# LED_DRIVE.net
KiCad netlist of a schematic drawn in Altium Designer
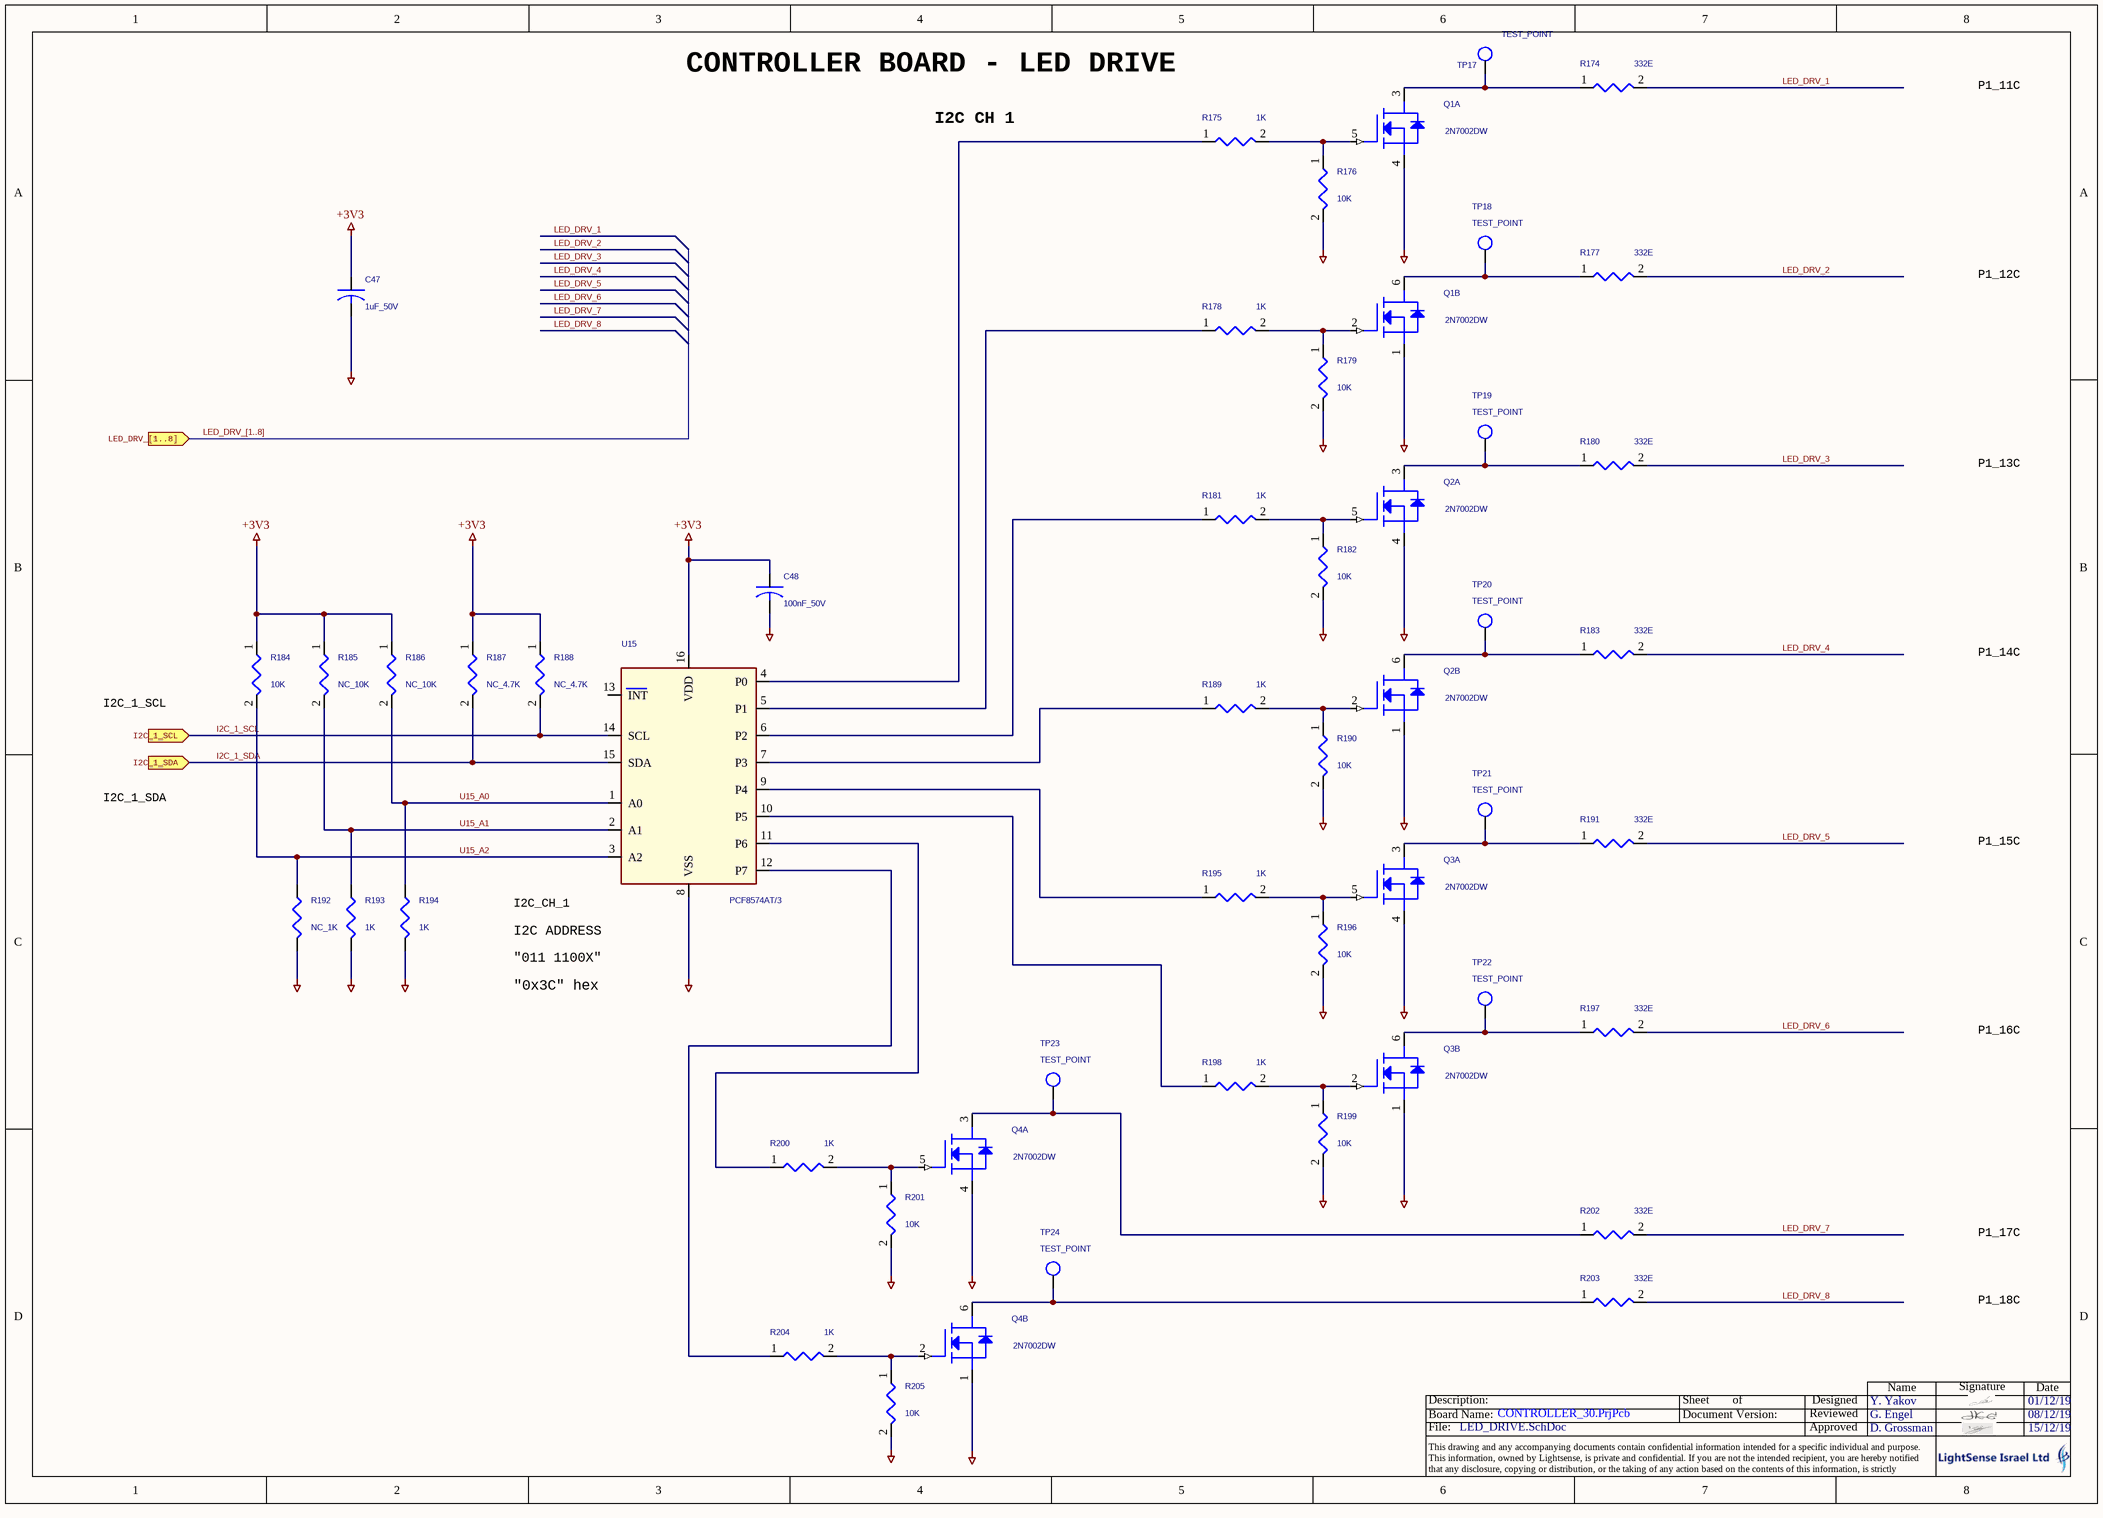
[diagram p0: LED_DRIVE.SchDoc]

(export (version "E")
  (design (tool "Eeschema 10.0.6"))
  (components
    (comp (ref "C47")
      (value "1uF_50V")
      (footprint "0805")
      (description "a")
      (fields (field (name "MFG") "Murata") (field (name "MNFCTR_PART_NUMBER") "TCJT106M016R0150"))
      (libsource (lib "*") (part "CAP"))
    )
    (comp (ref "C48")
      (value "100nF_50V")
      (footprint "0603")
      (description "CAP_SMT_0603_50V_X7R_10%")
      (fields (field (name "MFG") "KEMET"))
      (libsource (lib "*") (part "C"))
    )
    (comp (ref "Q1")
      (value "2N7002DW")
      (footprint "SOT_363")
      (fields (field (name "MFG") "DIODES"))
      (libsource (lib "*") (part "2N7002DW"))
    )
    (comp (ref "Q2")
      (value "2N7002DW")
      (footprint "SOT_363")
      (fields (field (name "MFG") "DIODES"))
      (libsource (lib "*") (part "2N7002DW"))
    )
    (comp (ref "Q3")
      (value "2N7002DW")
      (footprint "SOT_363")
      (fields (field (name "MFG") "DIODES"))
      (libsource (lib "*") (part "2N7002DW"))
    )
    (comp (ref "Q4")
      (value "2N7002DW")
      (footprint "SOT_363")
      (fields (field (name "MFG") "DIODES"))
      (libsource (lib "*") (part "2N7002DW"))
    )
    (comp (ref "R174")
      (value "332E")
      (footprint "R0603")
      (fields (field (name "MFG") "YAGEO"))
      (libsource (lib "*") (part "R"))
    )
    (comp (ref "R175")
      (value "1K")
      (footprint "R0603")
      (fields (field (name "MFG") "YAGEO"))
      (libsource (lib "*") (part "R"))
    )
    (comp (ref "R176")
      (value "10K")
      (footprint "R0603")
      (fields (field (name "MFG") "YAGEO"))
      (libsource (lib "*") (part "R"))
    )
    (comp (ref "R177")
      (value "332E")
      (footprint "R0603")
      (fields (field (name "MFG") "YAGEO"))
      (libsource (lib "*") (part "R"))
    )
    (comp (ref "R178")
      (value "1K")
      (footprint "R0603")
      (fields (field (name "MFG") "YAGEO"))
      (libsource (lib "*") (part "R"))
    )
    (comp (ref "R179")
      (value "10K")
      (footprint "R0603")
      (fields (field (name "MFG") "YAGEO"))
      (libsource (lib "*") (part "R"))
    )
    (comp (ref "R180")
      (value "332E")
      (footprint "R0603")
      (fields (field (name "MFG") "YAGEO"))
      (libsource (lib "*") (part "R"))
    )
    (comp (ref "R181")
      (value "1K")
      (footprint "R0603")
      (fields (field (name "MFG") "YAGEO"))
      (libsource (lib "*") (part "R"))
    )
    (comp (ref "R182")
      (value "10K")
      (footprint "R0603")
      (fields (field (name "MFG") "YAGEO"))
      (libsource (lib "*") (part "R"))
    )
    (comp (ref "R183")
      (value "332E")
      (footprint "R0603")
      (fields (field (name "MFG") "YAGEO"))
      (libsource (lib "*") (part "R"))
    )
    (comp (ref "R184")
      (value "10K")
      (footprint "R0603")
      (fields (field (name "MFG") "YAGEO"))
      (libsource (lib "*") (part "R"))
    )
    (comp (ref "R185")
      (value "NC_10K")
      (footprint "R0603")
      (fields (field (name "MFG") "YAGEO"))
      (libsource (lib "*") (part "R"))
    )
    (comp (ref "R186")
      (value "NC_10K")
      (footprint "R0603")
      (fields (field (name "MFG") "YAGEO"))
      (libsource (lib "*") (part "R"))
    )
    (comp (ref "R187")
      (value "NC_4.7K")
      (footprint "R0603")
      (fields (field (name "MFG") "YAGEO"))
      (libsource (lib "*") (part "R"))
    )
    (comp (ref "R188")
      (value "NC_4.7K")
      (footprint "R0603")
      (fields (field (name "MFG") "YAGEO"))
      (libsource (lib "*") (part "R"))
    )
    (comp (ref "R189")
      (value "1K")
      (footprint "R0603")
      (fields (field (name "MFG") "YAGEO"))
      (libsource (lib "*") (part "R"))
    )
    (comp (ref "R190")
      (value "10K")
      (footprint "R0603")
      (fields (field (name "MFG") "YAGEO"))
      (libsource (lib "*") (part "R"))
    )
    (comp (ref "R191")
      (value "332E")
      (footprint "R0603")
      (fields (field (name "MFG") "YAGEO"))
      (libsource (lib "*") (part "R"))
    )
    (comp (ref "R192")
      (value "NC_1K")
      (footprint "0603")
      (fields (field (name "MFG") "YAGEO"))
      (libsource (lib "*") (part "R_Dup1"))
    )
    (comp (ref "R193")
      (value "1K")
      (footprint "0603")
      (fields (field (name "MFG") "YAGEO"))
      (libsource (lib "*") (part "R_Dup1"))
    )
    (comp (ref "R194")
      (value "1K")
      (footprint "0603")
      (fields (field (name "MFG") "YAGEO"))
      (libsource (lib "*") (part "R_Dup1"))
    )
    (comp (ref "R195")
      (value "1K")
      (footprint "R0603")
      (fields (field (name "MFG") "YAGEO"))
      (libsource (lib "*") (part "R"))
    )
    (comp (ref "R196")
      (value "10K")
      (footprint "R0603")
      (fields (field (name "MFG") "YAGEO"))
      (libsource (lib "*") (part "R"))
    )
    (comp (ref "R197")
      (value "332E")
      (footprint "R0603")
      (fields (field (name "MFG") "YAGEO"))
      (libsource (lib "*") (part "R"))
    )
    (comp (ref "R198")
      (value "1K")
      (footprint "R0603")
      (fields (field (name "MFG") "YAGEO"))
      (libsource (lib "*") (part "R"))
    )
    (comp (ref "R199")
      (value "10K")
      (footprint "R0603")
      (fields (field (name "MFG") "YAGEO"))
      (libsource (lib "*") (part "R"))
    )
    (comp (ref "R200")
      (value "1K")
      (footprint "R0603")
      (fields (field (name "MFG") "YAGEO"))
      (libsource (lib "*") (part "R"))
    )
    (comp (ref "R201")
      (value "10K")
      (footprint "R0603")
      (fields (field (name "MFG") "YAGEO"))
      (libsource (lib "*") (part "R"))
    )
    (comp (ref "R202")
      (value "332E")
      (footprint "R0603")
      (fields (field (name "MFG") "YAGEO"))
      (libsource (lib "*") (part "R"))
    )
    (comp (ref "R203")
      (value "332E")
      (footprint "R0603")
      (fields (field (name "MFG") "YAGEO"))
      (libsource (lib "*") (part "R"))
    )
    (comp (ref "R204")
      (value "1K")
      (footprint "R0603")
      (fields (field (name "MFG") "YAGEO"))
      (libsource (lib "*") (part "R"))
    )
    (comp (ref "R205")
      (value "10K")
      (footprint "R0603")
      (fields (field (name "MFG") "YAGEO"))
      (libsource (lib "*") (part "R"))
    )
    (comp (ref "TP17")
      (value "TEST_POINT")
      (footprint "TH_1mm")
      (fields (field (name "MFG") "N.A."))
      (libsource (lib "*") (part "T POINT R"))
    )
    (comp (ref "TP18")
      (value "TEST_POINT")
      (footprint "TH_1mm")
      (fields (field (name "MFG") "N.A."))
      (libsource (lib "*") (part "T POINT R"))
    )
    (comp (ref "TP19")
      (value "TEST_POINT")
      (footprint "TH_1mm")
      (fields (field (name "MFG") "N.A."))
      (libsource (lib "*") (part "T POINT R"))
    )
    (comp (ref "TP20")
      (value "TEST_POINT")
      (footprint "TH_1mm")
      (fields (field (name "MFG") "N.A."))
      (libsource (lib "*") (part "T POINT R"))
    )
    (comp (ref "TP21")
      (value "TEST_POINT")
      (footprint "TH_1mm")
      (fields (field (name "MFG") "N.A."))
      (libsource (lib "*") (part "T POINT R"))
    )
    (comp (ref "TP22")
      (value "TEST_POINT")
      (footprint "TH_1mm")
      (fields (field (name "MFG") "N.A."))
      (libsource (lib "*") (part "T POINT R"))
    )
    (comp (ref "TP23")
      (value "TEST_POINT")
      (footprint "TH_1mm")
      (fields (field (name "MFG") "N.A."))
      (libsource (lib "*") (part "T POINT R"))
    )
    (comp (ref "TP24")
      (value "TEST_POINT")
      (footprint "TH_1mm")
      (fields (field (name "MFG") "N.A."))
      (libsource (lib "*") (part "T POINT R"))
    )
    (comp (ref "U15")
      (value "PCF8574AT/3")
      (footprint "SO_16")
      (description "PORT I2C, 8Bit, SO_16")
      (fields (field (name "MFG") "NXP"))
      (libsource (lib "*") (part "PCF8574_0"))
    )
  )
  (nets
    (net (code "1") (name "+3V3") (class "Default")
      (node (ref "C47") (pin "1") (pinfunction "1_1") (pintype "passive"))
      (node (ref "C48") (pin "1") (pinfunction "1_1") (pintype "passive"))
      (node (ref "R184") (pin "1") (pinfunction "1_1") (pintype "passive"))
      (node (ref "R185") (pin "1") (pinfunction "1_1") (pintype "passive"))
      (node (ref "R186") (pin "1") (pinfunction "1_1") (pintype "passive"))
      (node (ref "R187") (pin "1") (pinfunction "1_1") (pintype "passive"))
      (node (ref "R188") (pin "1") (pinfunction "1_1") (pintype "passive"))
      (node (ref "U15") (pin "16") (pinfunction "VDD_16") (pintype "passive"))
    )
    (net (code "2") (name "/I2C_1_SCL") (class "Default")
      (node (ref "R188") (pin "2") (pinfunction "2_2") (pintype "passive"))
      (node (ref "U15") (pin "14") (pinfunction "SCL_14") (pintype "passive"))
    )
    (net (code "3") (name "/I2C_1_SDA") (class "Default")
      (node (ref "R187") (pin "2") (pinfunction "2_2") (pintype "passive"))
      (node (ref "U15") (pin "15") (pinfunction "SDA_15") (pintype "passive"))
    )
    (net (code "4") (name "/LED_DRV_1") (class "Default")
      (node (ref "R174") (pin "2") (pinfunction "2_2") (pintype "passive"))
    )
    (net (code "5") (name "/LED_DRV_2") (class "Default")
      (node (ref "R177") (pin "2") (pinfunction "2_2") (pintype "passive"))
    )
    (net (code "6") (name "/LED_DRV_3") (class "Default")
      (node (ref "R180") (pin "2") (pinfunction "2_2") (pintype "passive"))
    )
    (net (code "7") (name "/LED_DRV_4") (class "Default")
      (node (ref "R183") (pin "2") (pinfunction "2_2") (pintype "passive"))
    )
    (net (code "8") (name "/LED_DRV_5") (class "Default")
      (node (ref "R191") (pin "2") (pinfunction "2_2") (pintype "passive"))
    )
    (net (code "9") (name "/LED_DRV_6") (class "Default")
      (node (ref "R197") (pin "2") (pinfunction "2_2") (pintype "passive"))
    )
    (net (code "10") (name "/LED_DRV_7") (class "Default")
      (node (ref "R202") (pin "2") (pinfunction "2_2") (pintype "passive"))
    )
    (net (code "11") (name "/LED_DRV_8") (class "Default")
      (node (ref "R203") (pin "2") (pinfunction "2_2") (pintype "passive"))
    )
    (net (code "13") (name "/U15_A0") (class "Default")
      (node (ref "R186") (pin "2") (pinfunction "2_2") (pintype "passive"))
      (node (ref "R194") (pin "1") (pinfunction "1_1") (pintype "passive"))
      (node (ref "U15") (pin "1") (pinfunction "A0_1") (pintype "passive"))
    )
    (net (code "14") (name "/U15_A1") (class "Default")
      (node (ref "R185") (pin "2") (pinfunction "2_2") (pintype "passive"))
      (node (ref "R193") (pin "1") (pinfunction "1_1") (pintype "passive"))
      (node (ref "U15") (pin "2") (pinfunction "A1_2") (pintype "passive"))
    )
    (net (code "15") (name "/U15_A2") (class "Default")
      (node (ref "R184") (pin "2") (pinfunction "2_2") (pintype "passive"))
      (node (ref "R192") (pin "1") (pinfunction "1_1") (pintype "passive"))
      (node (ref "U15") (pin "3") (pinfunction "A2_3") (pintype "passive"))
    )
    (net (code "16") (name "GND_CPU") (class "Default")
      (node (ref "C47") (pin "2") (pinfunction "2_2") (pintype "passive"))
      (node (ref "C48") (pin "2") (pinfunction "2_2") (pintype "passive"))
      (node (ref "Q1") (pin "1") (pinfunction "SOURCE_1") (pintype "passive"))
      (node (ref "Q1") (pin "4") (pinfunction "SOURCE_4") (pintype "passive"))
      (node (ref "Q2") (pin "1") (pinfunction "SOURCE_1") (pintype "passive"))
      (node (ref "Q2") (pin "4") (pinfunction "SOURCE_4") (pintype "passive"))
      (node (ref "Q3") (pin "1") (pinfunction "SOURCE_1") (pintype "passive"))
      (node (ref "Q3") (pin "4") (pinfunction "SOURCE_4") (pintype "passive"))
      (node (ref "Q4") (pin "1") (pinfunction "SOURCE_1") (pintype "passive"))
      (node (ref "Q4") (pin "4") (pinfunction "SOURCE_4") (pintype "passive"))
      (node (ref "R176") (pin "2") (pinfunction "2_2") (pintype "passive"))
      (node (ref "R179") (pin "2") (pinfunction "2_2") (pintype "passive"))
      (node (ref "R182") (pin "2") (pinfunction "2_2") (pintype "passive"))
      (node (ref "R190") (pin "2") (pinfunction "2_2") (pintype "passive"))
      (node (ref "R192") (pin "2") (pinfunction "2_2") (pintype "passive"))
      (node (ref "R193") (pin "2") (pinfunction "2_2") (pintype "passive"))
      (node (ref "R194") (pin "2") (pinfunction "2_2") (pintype "passive"))
      (node (ref "R196") (pin "2") (pinfunction "2_2") (pintype "passive"))
      (node (ref "R199") (pin "2") (pinfunction "2_2") (pintype "passive"))
      (node (ref "R201") (pin "2") (pinfunction "2_2") (pintype "passive"))
      (node (ref "R205") (pin "2") (pinfunction "2_2") (pintype "passive"))
      (node (ref "U15") (pin "8") (pinfunction "VSS_8") (pintype "passive"))
    )
    (net (code "17") (name "Net-(Q1A-DRAIN)") (class "Default")
      (node (ref "Q1") (pin "3") (pinfunction "DRAIN_3") (pintype "passive"))
      (node (ref "R174") (pin "1") (pinfunction "1_1") (pintype "passive"))
      (node (ref "TP17") (pin "1") (pinfunction "TP_1") (pintype "passive"))
    )
    (net (code "18") (name "Net-(Q1A-GATE)") (class "Default")
      (node (ref "Q1") (pin "5") (pinfunction "GATE_5") (pintype "input"))
      (node (ref "R175") (pin "2") (pinfunction "2_2") (pintype "passive"))
      (node (ref "R176") (pin "1") (pinfunction "1_1") (pintype "passive"))
    )
    (net (code "19") (name "Net-(Q1B-DRAIN)") (class "Default")
      (node (ref "Q1") (pin "6") (pinfunction "DRAIN_6") (pintype "passive"))
      (node (ref "R177") (pin "1") (pinfunction "1_1") (pintype "passive"))
      (node (ref "TP18") (pin "1") (pinfunction "TP_1") (pintype "passive"))
    )
    (net (code "20") (name "Net-(Q1B-GATE)") (class "Default")
      (node (ref "Q1") (pin "2") (pinfunction "GATE_2") (pintype "input"))
      (node (ref "R178") (pin "2") (pinfunction "2_2") (pintype "passive"))
      (node (ref "R179") (pin "1") (pinfunction "1_1") (pintype "passive"))
    )
    (net (code "21") (name "Net-(Q2A-DRAIN)") (class "Default")
      (node (ref "Q2") (pin "3") (pinfunction "DRAIN_3") (pintype "passive"))
      (node (ref "R180") (pin "1") (pinfunction "1_1") (pintype "passive"))
      (node (ref "TP19") (pin "1") (pinfunction "TP_1") (pintype "passive"))
    )
    (net (code "22") (name "Net-(Q2A-GATE)") (class "Default")
      (node (ref "Q2") (pin "5") (pinfunction "GATE_5") (pintype "input"))
      (node (ref "R181") (pin "2") (pinfunction "2_2") (pintype "passive"))
      (node (ref "R182") (pin "1") (pinfunction "1_1") (pintype "passive"))
    )
    (net (code "23") (name "Net-(Q2B-DRAIN)") (class "Default")
      (node (ref "Q2") (pin "6") (pinfunction "DRAIN_6") (pintype "passive"))
      (node (ref "R183") (pin "1") (pinfunction "1_1") (pintype "passive"))
      (node (ref "TP20") (pin "1") (pinfunction "TP_1") (pintype "passive"))
    )
    (net (code "24") (name "Net-(Q2B-GATE)") (class "Default")
      (node (ref "Q2") (pin "2") (pinfunction "GATE_2") (pintype "input"))
      (node (ref "R189") (pin "2") (pinfunction "2_2") (pintype "passive"))
      (node (ref "R190") (pin "1") (pinfunction "1_1") (pintype "passive"))
    )
    (net (code "25") (name "Net-(Q3A-DRAIN)") (class "Default")
      (node (ref "Q3") (pin "3") (pinfunction "DRAIN_3") (pintype "passive"))
      (node (ref "R191") (pin "1") (pinfunction "1_1") (pintype "passive"))
      (node (ref "TP21") (pin "1") (pinfunction "TP_1") (pintype "passive"))
    )
    (net (code "26") (name "Net-(Q3A-GATE)") (class "Default")
      (node (ref "Q3") (pin "5") (pinfunction "GATE_5") (pintype "input"))
      (node (ref "R195") (pin "2") (pinfunction "2_2") (pintype "passive"))
      (node (ref "R196") (pin "1") (pinfunction "1_1") (pintype "passive"))
    )
    (net (code "27") (name "Net-(Q3B-DRAIN)") (class "Default")
      (node (ref "Q3") (pin "6") (pinfunction "DRAIN_6") (pintype "passive"))
      (node (ref "R197") (pin "1") (pinfunction "1_1") (pintype "passive"))
      (node (ref "TP22") (pin "1") (pinfunction "TP_1") (pintype "passive"))
    )
    (net (code "28") (name "Net-(Q3B-GATE)") (class "Default")
      (node (ref "Q3") (pin "2") (pinfunction "GATE_2") (pintype "input"))
      (node (ref "R198") (pin "2") (pinfunction "2_2") (pintype "passive"))
      (node (ref "R199") (pin "1") (pinfunction "1_1") (pintype "passive"))
    )
    (net (code "29") (name "Net-(Q4A-DRAIN)") (class "Default")
      (node (ref "Q4") (pin "3") (pinfunction "DRAIN_3") (pintype "passive"))
      (node (ref "R202") (pin "1") (pinfunction "1_1") (pintype "passive"))
      (node (ref "TP23") (pin "1") (pinfunction "TP_1") (pintype "passive"))
    )
    (net (code "30") (name "Net-(Q4A-GATE)") (class "Default")
      (node (ref "Q4") (pin "5") (pinfunction "GATE_5") (pintype "input"))
      (node (ref "R200") (pin "2") (pinfunction "2_2") (pintype "passive"))
      (node (ref "R201") (pin "1") (pinfunction "1_1") (pintype "passive"))
    )
    (net (code "31") (name "Net-(Q4B-DRAIN)") (class "Default")
      (node (ref "Q4") (pin "6") (pinfunction "DRAIN_6") (pintype "passive"))
      (node (ref "R203") (pin "1") (pinfunction "1_1") (pintype "passive"))
      (node (ref "TP24") (pin "1") (pinfunction "TP_1") (pintype "passive"))
    )
    (net (code "32") (name "Net-(Q4B-GATE)") (class "Default")
      (node (ref "Q4") (pin "2") (pinfunction "GATE_2") (pintype "input"))
      (node (ref "R204") (pin "2") (pinfunction "2_2") (pintype "passive"))
      (node (ref "R205") (pin "1") (pinfunction "1_1") (pintype "passive"))
    )
    (net (code "33") (name "Net-(U15-P0)") (class "Default")
      (node (ref "R175") (pin "1") (pinfunction "1_1") (pintype "passive"))
      (node (ref "U15") (pin "4") (pinfunction "P0_4") (pintype "passive"))
    )
    (net (code "34") (name "Net-(U15-P1)") (class "Default")
      (node (ref "R178") (pin "1") (pinfunction "1_1") (pintype "passive"))
      (node (ref "U15") (pin "5") (pinfunction "P1_5") (pintype "passive"))
    )
    (net (code "35") (name "Net-(U15-P2)") (class "Default")
      (node (ref "R181") (pin "1") (pinfunction "1_1") (pintype "passive"))
      (node (ref "U15") (pin "6") (pinfunction "P2_6") (pintype "passive"))
    )
    (net (code "36") (name "Net-(U15-P3)") (class "Default")
      (node (ref "R189") (pin "1") (pinfunction "1_1") (pintype "passive"))
      (node (ref "U15") (pin "7") (pinfunction "P3_7") (pintype "passive"))
    )
    (net (code "37") (name "Net-(U15-P4)") (class "Default")
      (node (ref "R195") (pin "1") (pinfunction "1_1") (pintype "passive"))
      (node (ref "U15") (pin "9") (pinfunction "P4_9") (pintype "passive"))
    )
    (net (code "38") (name "Net-(U15-P5)") (class "Default")
      (node (ref "R198") (pin "1") (pinfunction "1_1") (pintype "passive"))
      (node (ref "U15") (pin "10") (pinfunction "P5_10") (pintype "passive"))
    )
    (net (code "39") (name "Net-(U15-P6)") (class "Default")
      (node (ref "R200") (pin "1") (pinfunction "1_1") (pintype "passive"))
      (node (ref "U15") (pin "11") (pinfunction "P6_11") (pintype "passive"))
    )
    (net (code "40") (name "Net-(U15-P7)") (class "Default")
      (node (ref "R204") (pin "1") (pinfunction "1_1") (pintype "passive"))
      (node (ref "U15") (pin "12") (pinfunction "P7_12") (pintype "passive"))
    )
    (net (code "41") (name "unconnected-(U15-INT-Pad13)") (class "Default")
      (node (ref "U15") (pin "13") (pinfunction "INT_13") (pintype "passive"))
    )
  )
)
